# EEG_Power_Connector.net
KiCad netlist of a schematic drawn in Altium Designer
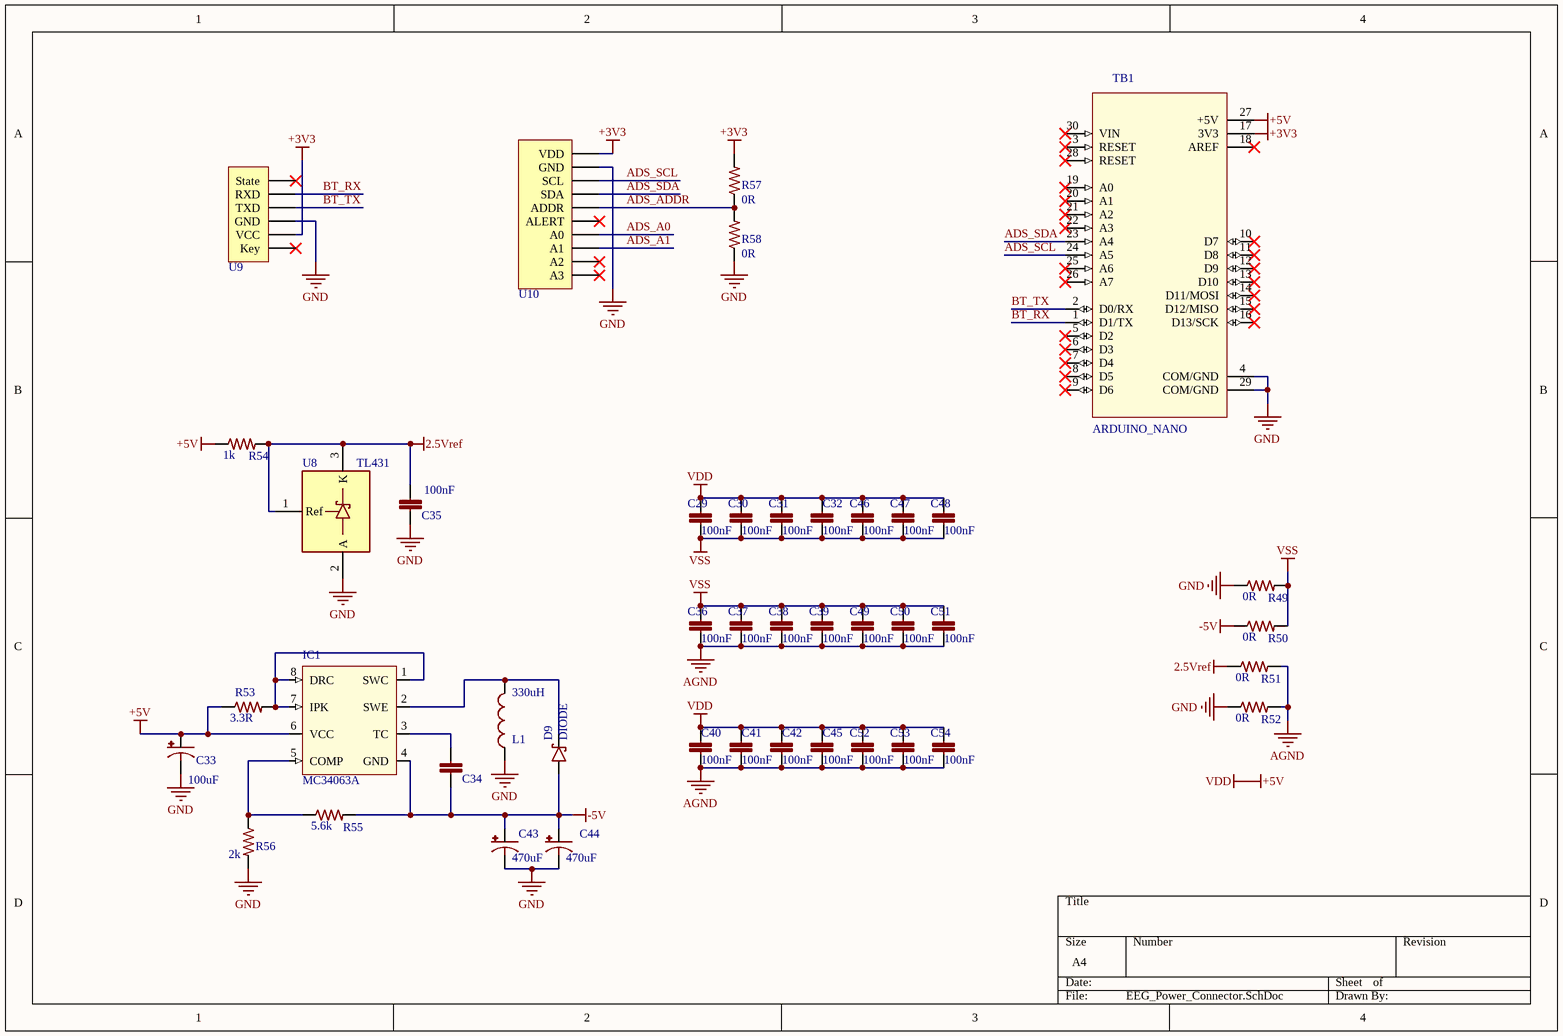
[diagram p0: EEG_Power_Connector.SchDoc]

(export (version "E")
  (design (tool "Eeschema 10.0.6"))
  (components
    (comp (ref "C29")
      (value "100nF")
      (footprint "C0805 - rounded")
      (description "Generic Capacitor SMD")
      (libsource (lib "rcl") (part "C-EU-SMD"))
    )
    (comp (ref "C30")
      (value "100nF")
      (footprint "C0805 - rounded")
      (description "Generic Capacitor SMD")
      (libsource (lib "rcl") (part "C-EU-SMD"))
    )
    (comp (ref "C31")
      (value "100nF")
      (footprint "C0805 - rounded")
      (description "Generic Capacitor SMD")
      (libsource (lib "rcl") (part "C-EU-SMD"))
    )
    (comp (ref "C32")
      (value "100nF")
      (footprint "C0805 - rounded")
      (description "Generic Capacitor SMD")
      (libsource (lib "rcl") (part "C-EU-SMD"))
    )
    (comp (ref "C33")
      (value "100uF")
      (footprint "E1,8-4")
      (description "Genereric Polarized Capacitor PTH")
      (libsource (lib "rcl") (part "CPOL-US-PTH"))
    )
    (comp (ref "C34")
      (value "~")
      (footprint "C0805 - rounded")
      (description "Generic Capacitor SMD")
      (libsource (lib "rcl") (part "C-EU-SMD"))
    )
    (comp (ref "C35")
      (value "100nF")
      (footprint "C0805 - rounded")
      (description "Generic Capacitor SMD")
      (libsource (lib "rcl") (part "C-EU-SMD"))
    )
    (comp (ref "C36")
      (value "100nF")
      (footprint "C0805 - rounded")
      (description "Generic Capacitor SMD")
      (libsource (lib "") (part "C-EU-SMD_1"))
    )
    (comp (ref "C37")
      (value "100nF")
      (footprint "C0805 - rounded")
      (description "Generic Capacitor SMD")
      (libsource (lib "rcl") (part "C-EU-SMD"))
    )
    (comp (ref "C38")
      (value "100nF")
      (footprint "C0805 - rounded")
      (description "Generic Capacitor SMD")
      (libsource (lib "rcl") (part "C-EU-SMD"))
    )
    (comp (ref "C39")
      (value "100nF")
      (footprint "C0805 - rounded")
      (description "Generic Capacitor SMD")
      (libsource (lib "rcl") (part "C-EU-SMD"))
    )
    (comp (ref "C40")
      (value "100nF")
      (footprint "C0805 - rounded")
      (description "Generic Capacitor SMD")
      (libsource (lib "rcl") (part "C-EU-SMD"))
    )
    (comp (ref "C41")
      (value "100nF")
      (footprint "C0805 - rounded")
      (description "Generic Capacitor SMD")
      (libsource (lib "rcl") (part "C-EU-SMD"))
    )
    (comp (ref "C42")
      (value "100nF")
      (footprint "C0805 - rounded")
      (description "Generic Capacitor SMD")
      (libsource (lib "rcl") (part "C-EU-SMD"))
    )
    (comp (ref "C43")
      (value "470uF")
      (footprint "E1,8-4")
      (description "Genereric Polarized Capacitor PTH")
      (libsource (lib "rcl") (part "CPOL-US-PTH"))
    )
    (comp (ref "C44")
      (value "470uF")
      (footprint "E1,8-4")
      (description "Genereric Polarized Capacitor PTH")
      (libsource (lib "rcl") (part "CPOL-US-PTH"))
    )
    (comp (ref "C45")
      (value "100nF")
      (footprint "C0805 - rounded")
      (description "Generic Capacitor SMD")
      (libsource (lib "rcl") (part "C-EU-SMD"))
    )
    (comp (ref "C46")
      (value "100nF")
      (footprint "C0805 - rounded")
      (description "Generic Capacitor SMD")
      (libsource (lib "rcl") (part "C-EU-SMD"))
    )
    (comp (ref "C47")
      (value "100nF")
      (footprint "C0805 - rounded")
      (description "Generic Capacitor SMD")
      (libsource (lib "rcl") (part "C-EU-SMD"))
    )
    (comp (ref "C48")
      (value "100nF")
      (footprint "C0805 - rounded")
      (description "Generic Capacitor SMD")
      (libsource (lib "rcl") (part "C-EU-SMD"))
    )
    (comp (ref "C49")
      (value "100nF")
      (footprint "C0805 - rounded")
      (description "Generic Capacitor SMD")
      (libsource (lib "rcl") (part "C-EU-SMD"))
    )
    (comp (ref "C50")
      (value "100nF")
      (footprint "C0805 - rounded")
      (description "Generic Capacitor SMD")
      (libsource (lib "rcl") (part "C-EU-SMD"))
    )
    (comp (ref "C51")
      (value "100nF")
      (footprint "C0805 - rounded")
      (description "Generic Capacitor SMD")
      (libsource (lib "rcl") (part "C-EU-SMD"))
    )
    (comp (ref "C52")
      (value "100nF")
      (footprint "C0805 - rounded")
      (description "Generic Capacitor SMD")
      (libsource (lib "rcl") (part "C-EU-SMD"))
    )
    (comp (ref "C53")
      (value "100nF")
      (footprint "C0805 - rounded")
      (description "Generic Capacitor SMD")
      (libsource (lib "rcl") (part "C-EU-SMD"))
    )
    (comp (ref "C54")
      (value "100nF")
      (footprint "C0805 - rounded")
      (description "Generic Capacitor SMD")
      (libsource (lib "rcl") (part "C-EU-SMD"))
    )
    (comp (ref "D9") (value "DIODE") (footprint "DO214AA") (libsource (lib "diode") (part "SCHOTTKY-DIODE")))
    (comp (ref "IC1")
      (value "MC34063A")
      (footprint "DIP8")
      (description "1.5-A Boost/Buck/Inverting Switching Regulator")
      (fields (field (name "MF") "Texas Instruments"))
      (libsource (lib "Misc") (part "MC34063A"))
    )
    (comp (ref "L1") (value "330uH") (footprint "L-PTH-12x9.5") (libsource (lib "rcl") (part "L-US-PTH")))
    (comp (ref "R49")
      (value "0R")
      (footprint "R0805 - rounded")
      (description "Generic Resistor SMD")
      (libsource (lib "rcl") (part "R-US-SMD"))
    )
    (comp (ref "R50")
      (value "0R")
      (footprint "R0805 - rounded")
      (description "Generic Resistor SMD")
      (libsource (lib "rcl") (part "R-US-SMD"))
    )
    (comp (ref "R51")
      (value "0R")
      (footprint "R0805 - rounded")
      (description "Generic Resistor SMD")
      (libsource (lib "rcl") (part "R-US-SMD"))
    )
    (comp (ref "R52")
      (value "0R")
      (footprint "R0805 - rounded")
      (description "Generic Resistor SMD")
      (libsource (lib "rcl") (part "R-US-SMD"))
    )
    (comp (ref "R53")
      (value "3.3R")
      (footprint "R0805 - rounded")
      (description "Generic Resistor SMD")
      (libsource (lib "rcl") (part "R-US-SMD"))
    )
    (comp (ref "R54")
      (value "1k")
      (footprint "R0805 - rounded")
      (description "Generic Resistor SMD")
      (libsource (lib "rcl") (part "R-US-SMD"))
    )
    (comp (ref "R55")
      (value "5.6k")
      (footprint "R0805 - rounded")
      (description "Generic Resistor SMD")
      (libsource (lib "rcl") (part "R-US-SMD"))
    )
    (comp (ref "R56")
      (value "2k")
      (footprint "R0805 - rounded")
      (description "Generic Resistor SMD")
      (libsource (lib "rcl") (part "R-US-SMD"))
    )
    (comp (ref "R57")
      (value "0R")
      (footprint "R0805 - rounded")
      (description "Generic Resistor SMD")
      (libsource (lib "rcl") (part "R-US-SMD"))
    )
    (comp (ref "R58")
      (value "0R")
      (footprint "R0805 - rounded")
      (description "Generic Resistor SMD")
      (libsource (lib "rcl") (part "R-US-SMD"))
    )
    (comp (ref "TB1")
      (value "ARDUINO_NANO")
      (footprint "ARDUINO_NANO_SHIELD")
      (description "Dev.kit: Arduino; UART; ICSP, USB B mini, pin strips")
      (fields (field (name "MP") "ARDUINO NANO") (field (name "MF") "Arduino"))
      (libsource (lib "devkits") (part "ARDUINO_NANO"))
    )
    (comp (ref "U8")
      (value "~")
      (footprint "TO92 - TL431")
      (description "Voltage References Rail Virtual Ground")
      (fields (field (name "PART NUMBER") "TL431"))
      (libsource (lib "Misc") (part "TL431"))
    )
    (comp (ref "U9")
      (value "HC-05/6")
      (footprint "HC-05/6 - upside down")
      (description "Bluetooth to Serial Port Module")
      (libsource (lib "devkits") (part "HC-05/6"))
    )
    (comp (ref "U10")
      (value "ADS1115 module")
      (footprint "ADS1115 Module - horizontal")
      (description "16Bit I2C ADC+PGA")
      (libsource (lib "devkits") (part "ADS1115 module"))
    )
  )
  (nets
    (net (code "1") (name "+3V3") (class "Default")
      (node (ref "R57") (pin "2") (pinfunction "2_2") (pintype "passive"))
      (node (ref "TB1") (pin "17") (pinfunction "3V3_17") (pintype "power_in"))
      (node (ref "U10") (pin "1") (pinfunction "VDD_1") (pintype "passive"))
      (node (ref "U9") (pin "5") (pinfunction "VCC_5") (pintype "passive"))
    )
    (net (code "2") (name "+5V") (class "Default")
      (node (ref "C29") (pin "2") (pinfunction "2_2") (pintype "passive"))
      (node (ref "C30") (pin "2") (pinfunction "2_2") (pintype "passive"))
      (node (ref "C31") (pin "2") (pinfunction "2_2") (pintype "passive"))
      (node (ref "C32") (pin "2") (pinfunction "2_2") (pintype "passive"))
      (node (ref "C33") (pin "+") (pinfunction "+_+") (pintype "passive"))
      (node (ref "C40") (pin "2") (pinfunction "2_2") (pintype "passive"))
      (node (ref "C41") (pin "2") (pinfunction "2_2") (pintype "passive"))
      (node (ref "C42") (pin "2") (pinfunction "2_2") (pintype "passive"))
      (node (ref "C45") (pin "2") (pinfunction "2_2") (pintype "passive"))
      (node (ref "C46") (pin "2") (pinfunction "2_2") (pintype "passive"))
      (node (ref "C47") (pin "2") (pinfunction "2_2") (pintype "passive"))
      (node (ref "C48") (pin "2") (pinfunction "2_2") (pintype "passive"))
      (node (ref "C52") (pin "2") (pinfunction "2_2") (pintype "passive"))
      (node (ref "C53") (pin "2") (pinfunction "2_2") (pintype "passive"))
      (node (ref "C54") (pin "2") (pinfunction "2_2") (pintype "passive"))
      (node (ref "IC1") (pin "6") (pinfunction "VCC_6") (pintype "power_in"))
      (node (ref "R53") (pin "1") (pinfunction "1_1") (pintype "passive"))
      (node (ref "R54") (pin "1") (pinfunction "1_1") (pintype "passive"))
      (node (ref "TB1") (pin "27") (pinfunction "+5V_27") (pintype "power_in"))
    )
    (net (code "3") (name "-5V") (class "Default")
      (node (ref "C34") (pin "1") (pinfunction "1_1") (pintype "passive"))
      (node (ref "C43") (pin "+") (pinfunction "+_+") (pintype "passive"))
      (node (ref "C44") (pin "+") (pinfunction "+_+") (pintype "passive"))
      (node (ref "D9") (pin "A") (pinfunction "A_A") (pintype "passive"))
      (node (ref "IC1") (pin "4") (pinfunction "GND_4") (pintype "power_in"))
      (node (ref "R50") (pin "1") (pinfunction "1_1") (pintype "passive"))
      (node (ref "R55") (pin "2") (pinfunction "2_2") (pintype "passive"))
    )
    (net (code "4") (name "/ADS_A0") (class "Default")
      (node (ref "U10") (pin "7") (pinfunction "A0_7") (pintype "passive"))
    )
    (net (code "5") (name "/ADS_A1") (class "Default")
      (node (ref "U10") (pin "8") (pinfunction "A1_8") (pintype "passive"))
    )
    (net (code "6") (name "/ADS_ADDR") (class "Default")
      (node (ref "R57") (pin "1") (pinfunction "1_1") (pintype "passive"))
      (node (ref "R58") (pin "2") (pinfunction "2_2") (pintype "passive"))
      (node (ref "U10") (pin "5") (pinfunction "ADDR_5") (pintype "passive"))
    )
    (net (code "7") (name "/ADS_SCL") (class "Default")
      (node (ref "TB1") (pin "24") (pinfunction "A5_24") (pintype "input"))
      (node (ref "U10") (pin "3") (pinfunction "SCL_3") (pintype "passive"))
    )
    (net (code "8") (name "/ADS_SDA") (class "Default")
      (node (ref "TB1") (pin "23") (pinfunction "A4_23") (pintype "input"))
      (node (ref "U10") (pin "4") (pinfunction "SDA_4") (pintype "passive"))
    )
    (net (code "9") (name "/BT_RX") (class "Default")
      (node (ref "TB1") (pin "1") (pinfunction "D1/TX_1") (pintype "bidirectional"))
      (node (ref "U9") (pin "2") (pinfunction "RXD_2") (pintype "passive"))
    )
    (net (code "10") (name "/BT_TX") (class "Default")
      (node (ref "TB1") (pin "2") (pinfunction "D0/RX_2") (pintype "bidirectional"))
      (node (ref "U9") (pin "3") (pinfunction "TXD_3") (pintype "passive"))
    )
    (net (code "11") (name "2.5Vref") (class "Default")
      (node (ref "C35") (pin "2") (pinfunction "2_2") (pintype "passive"))
      (node (ref "R51") (pin "1") (pinfunction "1_1") (pintype "passive"))
      (node (ref "R54") (pin "2") (pinfunction "2_2") (pintype "passive"))
      (node (ref "U8") (pin "1") (pinfunction "Ref_1") (pintype "power_in"))
      (node (ref "U8") (pin "3") (pinfunction "K_3") (pintype "passive"))
    )
    (net (code "12") (name "AGND") (class "Default")
      (node (ref "C36") (pin "2") (pinfunction "2_2") (pintype "passive"))
      (node (ref "C37") (pin "1") (pinfunction "1_1") (pintype "passive"))
      (node (ref "C38") (pin "1") (pinfunction "1_1") (pintype "passive"))
      (node (ref "C39") (pin "1") (pinfunction "1_1") (pintype "passive"))
      (node (ref "C40") (pin "1") (pinfunction "1_1") (pintype "passive"))
      (node (ref "C41") (pin "1") (pinfunction "1_1") (pintype "passive"))
      (node (ref "C42") (pin "1") (pinfunction "1_1") (pintype "passive"))
      (node (ref "C45") (pin "1") (pinfunction "1_1") (pintype "passive"))
      (node (ref "C49") (pin "1") (pinfunction "1_1") (pintype "passive"))
      (node (ref "C50") (pin "1") (pinfunction "1_1") (pintype "passive"))
      (node (ref "C51") (pin "1") (pinfunction "1_1") (pintype "passive"))
      (node (ref "C52") (pin "1") (pinfunction "1_1") (pintype "passive"))
      (node (ref "C53") (pin "1") (pinfunction "1_1") (pintype "passive"))
      (node (ref "C54") (pin "1") (pinfunction "1_1") (pintype "passive"))
      (node (ref "R51") (pin "2") (pinfunction "2_2") (pintype "passive"))
      (node (ref "R52") (pin "2") (pinfunction "2_2") (pintype "passive"))
    )
    (net (code "13") (name "GND") (class "Default")
      (node (ref "C33") (pin "-") (pinfunction "-_-") (pintype "passive"))
      (node (ref "C35") (pin "1") (pinfunction "1_1") (pintype "passive"))
      (node (ref "C43") (pin "-") (pinfunction "-_-") (pintype "passive"))
      (node (ref "C44") (pin "-") (pinfunction "-_-") (pintype "passive"))
      (node (ref "L1") (pin "1") (pinfunction "1_1") (pintype "passive"))
      (node (ref "R49") (pin "1") (pinfunction "1_1") (pintype "passive"))
      (node (ref "R52") (pin "1") (pinfunction "1_1") (pintype "passive"))
      (node (ref "R56") (pin "2") (pinfunction "2_2") (pintype "passive"))
      (node (ref "R58") (pin "1") (pinfunction "1_1") (pintype "passive"))
      (node (ref "TB1") (pin "29") (pinfunction "COM/GND_29") (pintype "power_in"))
      (node (ref "TB1") (pin "4") (pinfunction "COM/GND_4") (pintype "power_in"))
      (node (ref "U10") (pin "2") (pinfunction "GND_2") (pintype "passive"))
      (node (ref "U8") (pin "2") (pinfunction "A_2") (pintype "power_in"))
      (node (ref "U9") (pin "4") (pinfunction "GND_4") (pintype "passive"))
    )
    (net (code "14") (name "Net-(IC1-COMP)") (class "Default")
      (node (ref "IC1") (pin "5") (pinfunction "COMP_5") (pintype "input"))
      (node (ref "R55") (pin "1") (pinfunction "1_1") (pintype "passive"))
      (node (ref "R56") (pin "1") (pinfunction "1_1") (pintype "passive"))
    )
    (net (code "15") (name "Net-(IC1-DRC)") (class "Default")
      (node (ref "IC1") (pin "1") (pinfunction "SWC_1") (pintype "bidirectional"))
      (node (ref "IC1") (pin "7") (pinfunction "IPK_7") (pintype "input"))
      (node (ref "IC1") (pin "8") (pinfunction "DRC_8") (pintype "input"))
      (node (ref "R53") (pin "2") (pinfunction "2_2") (pintype "passive"))
    )
    (net (code "16") (name "Net-(IC1-SWE)") (class "Default")
      (node (ref "D9") (pin "C") (pinfunction "C_C") (pintype "passive"))
      (node (ref "IC1") (pin "2") (pinfunction "SWE_2") (pintype "bidirectional"))
      (node (ref "L1") (pin "2") (pinfunction "2_2") (pintype "passive"))
    )
    (net (code "17") (name "Net-(IC1-TC)") (class "Default")
      (node (ref "C34") (pin "2") (pinfunction "2_2") (pintype "passive"))
      (node (ref "IC1") (pin "3") (pinfunction "TC_3") (pintype "passive"))
    )
    (net (code "18") (name "VSS") (class "Default")
      (node (ref "C29") (pin "1") (pinfunction "1_1") (pintype "passive"))
      (node (ref "C30") (pin "1") (pinfunction "1_1") (pintype "passive"))
      (node (ref "C31") (pin "1") (pinfunction "1_1") (pintype "passive"))
      (node (ref "C32") (pin "1") (pinfunction "1_1") (pintype "passive"))
      (node (ref "C36") (pin "1") (pinfunction "1_1") (pintype "passive"))
      (node (ref "C37") (pin "2") (pinfunction "2_2") (pintype "passive"))
      (node (ref "C38") (pin "2") (pinfunction "2_2") (pintype "passive"))
      (node (ref "C39") (pin "2") (pinfunction "2_2") (pintype "passive"))
      (node (ref "C46") (pin "1") (pinfunction "1_1") (pintype "passive"))
      (node (ref "C47") (pin "1") (pinfunction "1_1") (pintype "passive"))
      (node (ref "C48") (pin "1") (pinfunction "1_1") (pintype "passive"))
      (node (ref "C49") (pin "2") (pinfunction "2_2") (pintype "passive"))
      (node (ref "C50") (pin "2") (pinfunction "2_2") (pintype "passive"))
      (node (ref "C51") (pin "2") (pinfunction "2_2") (pintype "passive"))
      (node (ref "R49") (pin "2") (pinfunction "2_2") (pintype "passive"))
      (node (ref "R50") (pin "2") (pinfunction "2_2") (pintype "passive"))
    )
    (net (code "19") (name "unconnected-(TB1-A0-Pad19)") (class "Default")
      (node (ref "TB1") (pin "19") (pinfunction "A0_19") (pintype "input+no_connect"))
    )
    (net (code "20") (name "unconnected-(TB1-A1-Pad20)") (class "Default")
      (node (ref "TB1") (pin "20") (pinfunction "A1_20") (pintype "input+no_connect"))
    )
    (net (code "21") (name "unconnected-(TB1-A2-Pad21)") (class "Default")
      (node (ref "TB1") (pin "21") (pinfunction "A2_21") (pintype "input+no_connect"))
    )
    (net (code "22") (name "unconnected-(TB1-A3-Pad22)") (class "Default")
      (node (ref "TB1") (pin "22") (pinfunction "A3_22") (pintype "input+no_connect"))
    )
    (net (code "23") (name "unconnected-(TB1-A6-Pad25)") (class "Default")
      (node (ref "TB1") (pin "25") (pinfunction "A6_25") (pintype "input+no_connect"))
    )
    (net (code "24") (name "unconnected-(TB1-A7-Pad26)") (class "Default")
      (node (ref "TB1") (pin "26") (pinfunction "A7_26") (pintype "input+no_connect"))
    )
    (net (code "25") (name "unconnected-(TB1-AREF-Pad18)") (class "Default")
      (node (ref "TB1") (pin "18") (pinfunction "AREF_18") (pintype "power_in+no_connect"))
    )
    (net (code "26") (name "unconnected-(TB1-D2-Pad5)") (class "Default")
      (node (ref "TB1") (pin "5") (pinfunction "D2_5") (pintype "bidirectional+no_connect"))
    )
    (net (code "27") (name "unconnected-(TB1-D3-Pad6)") (class "Default")
      (node (ref "TB1") (pin "6") (pinfunction "D3_6") (pintype "bidirectional+no_connect"))
    )
    (net (code "28") (name "unconnected-(TB1-D4-Pad7)") (class "Default")
      (node (ref "TB1") (pin "7") (pinfunction "D4_7") (pintype "bidirectional+no_connect"))
    )
    (net (code "29") (name "unconnected-(TB1-D5-Pad8)") (class "Default")
      (node (ref "TB1") (pin "8") (pinfunction "D5_8") (pintype "bidirectional+no_connect"))
    )
    (net (code "30") (name "unconnected-(TB1-D6-Pad9)") (class "Default")
      (node (ref "TB1") (pin "9") (pinfunction "D6_9") (pintype "bidirectional+no_connect"))
    )
    (net (code "31") (name "unconnected-(TB1-D7-Pad10)") (class "Default")
      (node (ref "TB1") (pin "10") (pinfunction "D7_10") (pintype "bidirectional+no_connect"))
    )
    (net (code "32") (name "unconnected-(TB1-D8-Pad11)") (class "Default")
      (node (ref "TB1") (pin "11") (pinfunction "D8_11") (pintype "bidirectional+no_connect"))
    )
    (net (code "33") (name "unconnected-(TB1-D9-Pad12)") (class "Default")
      (node (ref "TB1") (pin "12") (pinfunction "D9_12") (pintype "bidirectional+no_connect"))
    )
    (net (code "34") (name "unconnected-(TB1-D10-Pad13)") (class "Default")
      (node (ref "TB1") (pin "13") (pinfunction "D10_13") (pintype "bidirectional+no_connect"))
    )
    (net (code "35") (name "unconnected-(TB1-D11{slash}MOSI-Pad14)") (class "Default")
      (node (ref "TB1") (pin "14") (pinfunction "D11/MOSI_14") (pintype "bidirectional+no_connect"))
    )
    (net (code "36") (name "unconnected-(TB1-D12{slash}MISO-Pad15)") (class "Default")
      (node (ref "TB1") (pin "15") (pinfunction "D12/MISO_15") (pintype "bidirectional+no_connect"))
    )
    (net (code "37") (name "unconnected-(TB1-D13{slash}SCK-Pad16)") (class "Default")
      (node (ref "TB1") (pin "16") (pinfunction "D13/SCK_16") (pintype "bidirectional+no_connect"))
    )
    (net (code "38") (name "unconnected-(TB1-RESET-Pad3)") (class "Default")
      (node (ref "TB1") (pin "3") (pinfunction "RESET_3") (pintype "input+no_connect"))
    )
    (net (code "39") (name "unconnected-(TB1-RESET-Pad28)") (class "Default")
      (node (ref "TB1") (pin "28") (pinfunction "RESET_28") (pintype "input+no_connect"))
    )
    (net (code "40") (name "unconnected-(TB1-VIN-Pad30)") (class "Default")
      (node (ref "TB1") (pin "30") (pinfunction "VIN_30") (pintype "input+no_connect"))
    )
    (net (code "41") (name "unconnected-(U9-Key-Pad6)") (class "Default")
      (node (ref "U9") (pin "6") (pinfunction "Key_6") (pintype "passive+no_connect"))
    )
    (net (code "42") (name "unconnected-(U9-State-Pad1)") (class "Default")
      (node (ref "U9") (pin "1") (pinfunction "State_1") (pintype "passive+no_connect"))
    )
    (net (code "43") (name "unconnected-(U10-A2-Pad9)") (class "Default")
      (node (ref "U10") (pin "9") (pinfunction "A2_9") (pintype "passive+no_connect"))
    )
    (net (code "44") (name "unconnected-(U10-A3-Pad10)") (class "Default")
      (node (ref "U10") (pin "10") (pinfunction "A3_10") (pintype "passive+no_connect"))
    )
    (net (code "45") (name "unconnected-(U10-ALERT-Pad6)") (class "Default")
      (node (ref "U10") (pin "6") (pinfunction "ALERT_6") (pintype "passive+no_connect"))
    )
  )
)
